# rs485.net
KiCad netlist of a schematic drawn in Altium Designer
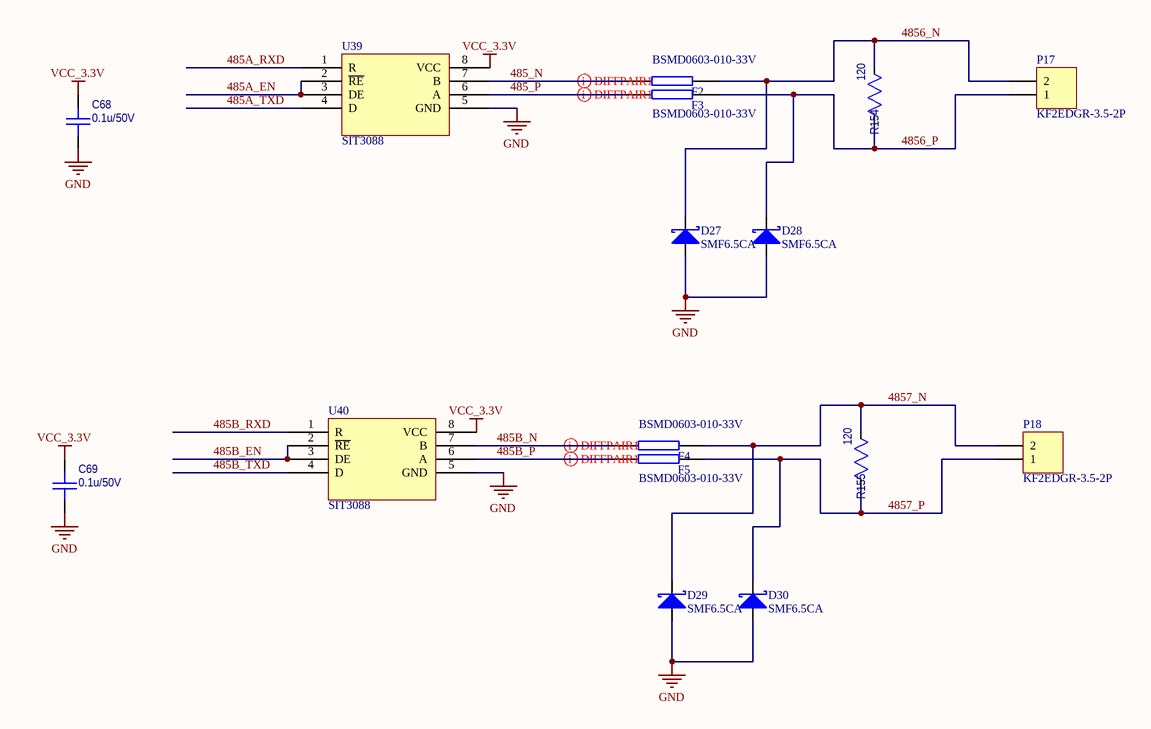
[diagram p0: rs485.SchDoc]

(export (version "E")
  (design (tool "Eeschema 10.0.6"))
  (components
    (comp (ref "C68")
      (value "0.1u/50V")
      (footprint "CAPC1608X092N_0603")
      (description "Capacitor, MLCC")
      (fields (field (name "PARTNUMBER") "C0603C104M5RACTU"))
      (libsource (lib "Karl") (part "Capacitor_0603"))
    )
    (comp (ref "C69")
      (value "0.1u/50V")
      (footprint "CAPC1608X092N_0603")
      (description "Capacitor, MLCC")
      (fields (field (name "PARTNUMBER") "C0603C104M5RACTU"))
      (libsource (lib "Karl") (part "Capacitor_0603"))
    )
    (comp (ref "D27") (value "SMF6.5CA") (footprint "SOD123") (libsource (lib "*") (part "DIODE S")))
    (comp (ref "D28") (value "SMF6.5CA") (footprint "SOD123") (libsource (lib "*") (part "DIODE S")))
    (comp (ref "D29") (value "SMF6.5CA") (footprint "SOD123") (libsource (lib "*") (part "DIODE S")))
    (comp (ref "D30") (value "SMF6.5CA") (footprint "SOD123") (libsource (lib "*") (part "DIODE S")))
    (comp (ref "F2") (value "BSMD0603-010-33V") (footprint "0603R") (libsource (lib "*") (part "RES2")))
    (comp (ref "F3") (value "BSMD0603-010-33V") (footprint "0603R") (libsource (lib "*") (part "RES2")))
    (comp (ref "F4") (value "BSMD0603-010-33V") (footprint "0603R") (libsource (lib "*") (part "RES2")))
    (comp (ref "F5") (value "BSMD0603-010-33V") (footprint "0603R") (libsource (lib "*") (part "RES2")))
    (comp (ref "P17")
      (value "KF2EDGR-3.5-2P")
      (footprint "CONN-TH_P3.50_KF2EDGR-3.5-2P:CONN-TH_P3.50_KF2EDGR-3.5-2P")
      (description "Header, 2-Pin")
      (libsource (lib "Miscellaneous Connectors") (part "Header 2"))
    )
    (comp (ref "P18")
      (value "KF2EDGR-3.5-2P")
      (footprint "CONN-TH_P3.50_KF2EDGR-3.5-2P:CONN-TH_P3.50_KF2EDGR-3.5-2P")
      (description "Header, 2-Pin")
      (libsource (lib "Miscellaneous Connectors") (part "Header 2"))
    )
    (comp (ref "R154")
      (value "120")
      (footprint "RESC1608X055N_0603")
      (description "Resistor, Standard")
      (fields (field (name "PARTNUMBER") "RC0603FR-1075KL"))
      (libsource (lib "Karl") (part "Resistor_0603"))
    )
    (comp (ref "R155")
      (value "120")
      (footprint "RESC1608X055N_0603")
      (description "Resistor, Standard")
      (fields (field (name "PARTNUMBER") "RC0603FR-1075KL"))
      (libsource (lib "Karl") (part "Resistor_0603"))
    )
    (comp (ref "U39") (value "SIT3088") (footprint "so-8") (libsource (lib "Schlib1") (part "SN65HVD06D")))
    (comp (ref "U40") (value "SIT3088") (footprint "so-8") (libsource (lib "Schlib1") (part "SN65HVD06D")))
  )
  (nets
    (net (code "1") (name "/485A_EN") (class "Default")
      (node (ref "U39") (pin "2") (pinfunction "~{RE}_2") (pintype "passive"))
      (node (ref "U39") (pin "3") (pinfunction "DE_3") (pintype "passive"))
    )
    (net (code "2") (name "/485A_RXD") (class "Default")
      (node (ref "U39") (pin "1") (pinfunction "R_1") (pintype "passive"))
    )
    (net (code "3") (name "/485A_TXD") (class "Default")
      (node (ref "U39") (pin "4") (pinfunction "D_4") (pintype "passive"))
    )
    (net (code "4") (name "/485B_EN") (class "Default")
      (node (ref "U40") (pin "2") (pinfunction "~{RE}_2") (pintype "passive"))
      (node (ref "U40") (pin "3") (pinfunction "DE_3") (pintype "passive"))
    )
    (net (code "5") (name "/485B_N") (class "Default")
      (node (ref "F4") (pin "2") (pinfunction "2_2") (pintype "passive"))
      (node (ref "U40") (pin "7") (pinfunction "B_7") (pintype "passive"))
    )
    (net (code "6") (name "/485B_P") (class "Default")
      (node (ref "F5") (pin "2") (pinfunction "2_2") (pintype "passive"))
      (node (ref "U40") (pin "6") (pinfunction "A_6") (pintype "passive"))
    )
    (net (code "7") (name "/485B_RXD") (class "Default")
      (node (ref "U40") (pin "1") (pinfunction "R_1") (pintype "passive"))
    )
    (net (code "8") (name "/485B_TXD") (class "Default")
      (node (ref "U40") (pin "4") (pinfunction "D_4") (pintype "passive"))
    )
    (net (code "9") (name "/485_N") (class "Default")
      (node (ref "F2") (pin "2") (pinfunction "2_2") (pintype "passive"))
      (node (ref "U39") (pin "7") (pinfunction "B_7") (pintype "passive"))
    )
    (net (code "10") (name "/485_P") (class "Default")
      (node (ref "F3") (pin "2") (pinfunction "2_2") (pintype "passive"))
      (node (ref "U39") (pin "6") (pinfunction "A_6") (pintype "passive"))
    )
    (net (code "11") (name "/4856_N") (class "Default")
      (node (ref "D27") (pin "2") (pinfunction "K_2") (pintype "passive"))
      (node (ref "F2") (pin "1") (pinfunction "1_1") (pintype "passive"))
      (node (ref "P17") (pin "2") (pinfunction "2_2") (pintype "passive"))
      (node (ref "R154") (pin "1") (pinfunction "1_1") (pintype "passive"))
    )
    (net (code "12") (name "/4856_P") (class "Default")
      (node (ref "D28") (pin "2") (pinfunction "K_2") (pintype "passive"))
      (node (ref "F3") (pin "1") (pinfunction "1_1") (pintype "passive"))
      (node (ref "P17") (pin "1") (pinfunction "1_1") (pintype "passive"))
      (node (ref "R154") (pin "2") (pinfunction "2_2") (pintype "passive"))
    )
    (net (code "13") (name "/4857_N") (class "Default")
      (node (ref "D29") (pin "2") (pinfunction "K_2") (pintype "passive"))
      (node (ref "F4") (pin "1") (pinfunction "1_1") (pintype "passive"))
      (node (ref "P18") (pin "2") (pinfunction "2_2") (pintype "passive"))
      (node (ref "R155") (pin "1") (pinfunction "1_1") (pintype "passive"))
    )
    (net (code "14") (name "/4857_P") (class "Default")
      (node (ref "D30") (pin "2") (pinfunction "K_2") (pintype "passive"))
      (node (ref "F5") (pin "1") (pinfunction "1_1") (pintype "passive"))
      (node (ref "P18") (pin "1") (pinfunction "1_1") (pintype "passive"))
      (node (ref "R155") (pin "2") (pinfunction "2_2") (pintype "passive"))
    )
    (net (code "15") (name "GND") (class "Default")
      (node (ref "C68") (pin "2") (pinfunction "2_2") (pintype "passive"))
      (node (ref "C69") (pin "2") (pinfunction "2_2") (pintype "passive"))
      (node (ref "D27") (pin "1") (pinfunction "A_1") (pintype "passive"))
      (node (ref "D28") (pin "1") (pinfunction "A_1") (pintype "passive"))
      (node (ref "D29") (pin "1") (pinfunction "A_1") (pintype "passive"))
      (node (ref "D30") (pin "1") (pinfunction "A_1") (pintype "passive"))
      (node (ref "U39") (pin "5") (pinfunction "GND_5") (pintype "passive"))
      (node (ref "U40") (pin "5") (pinfunction "GND_5") (pintype "passive"))
    )
    (net (code "16") (name "VCC_3.3V") (class "Default")
      (node (ref "C68") (pin "1") (pinfunction "1_1") (pintype "passive"))
      (node (ref "C69") (pin "1") (pinfunction "1_1") (pintype "passive"))
      (node (ref "U39") (pin "8") (pinfunction "VCC_8") (pintype "passive"))
      (node (ref "U40") (pin "8") (pinfunction "VCC_8") (pintype "passive"))
    )
  )
)
